# TommyPROM-8755A_Nano.net
KiCad netlist of a schematic drawn in EAGLE
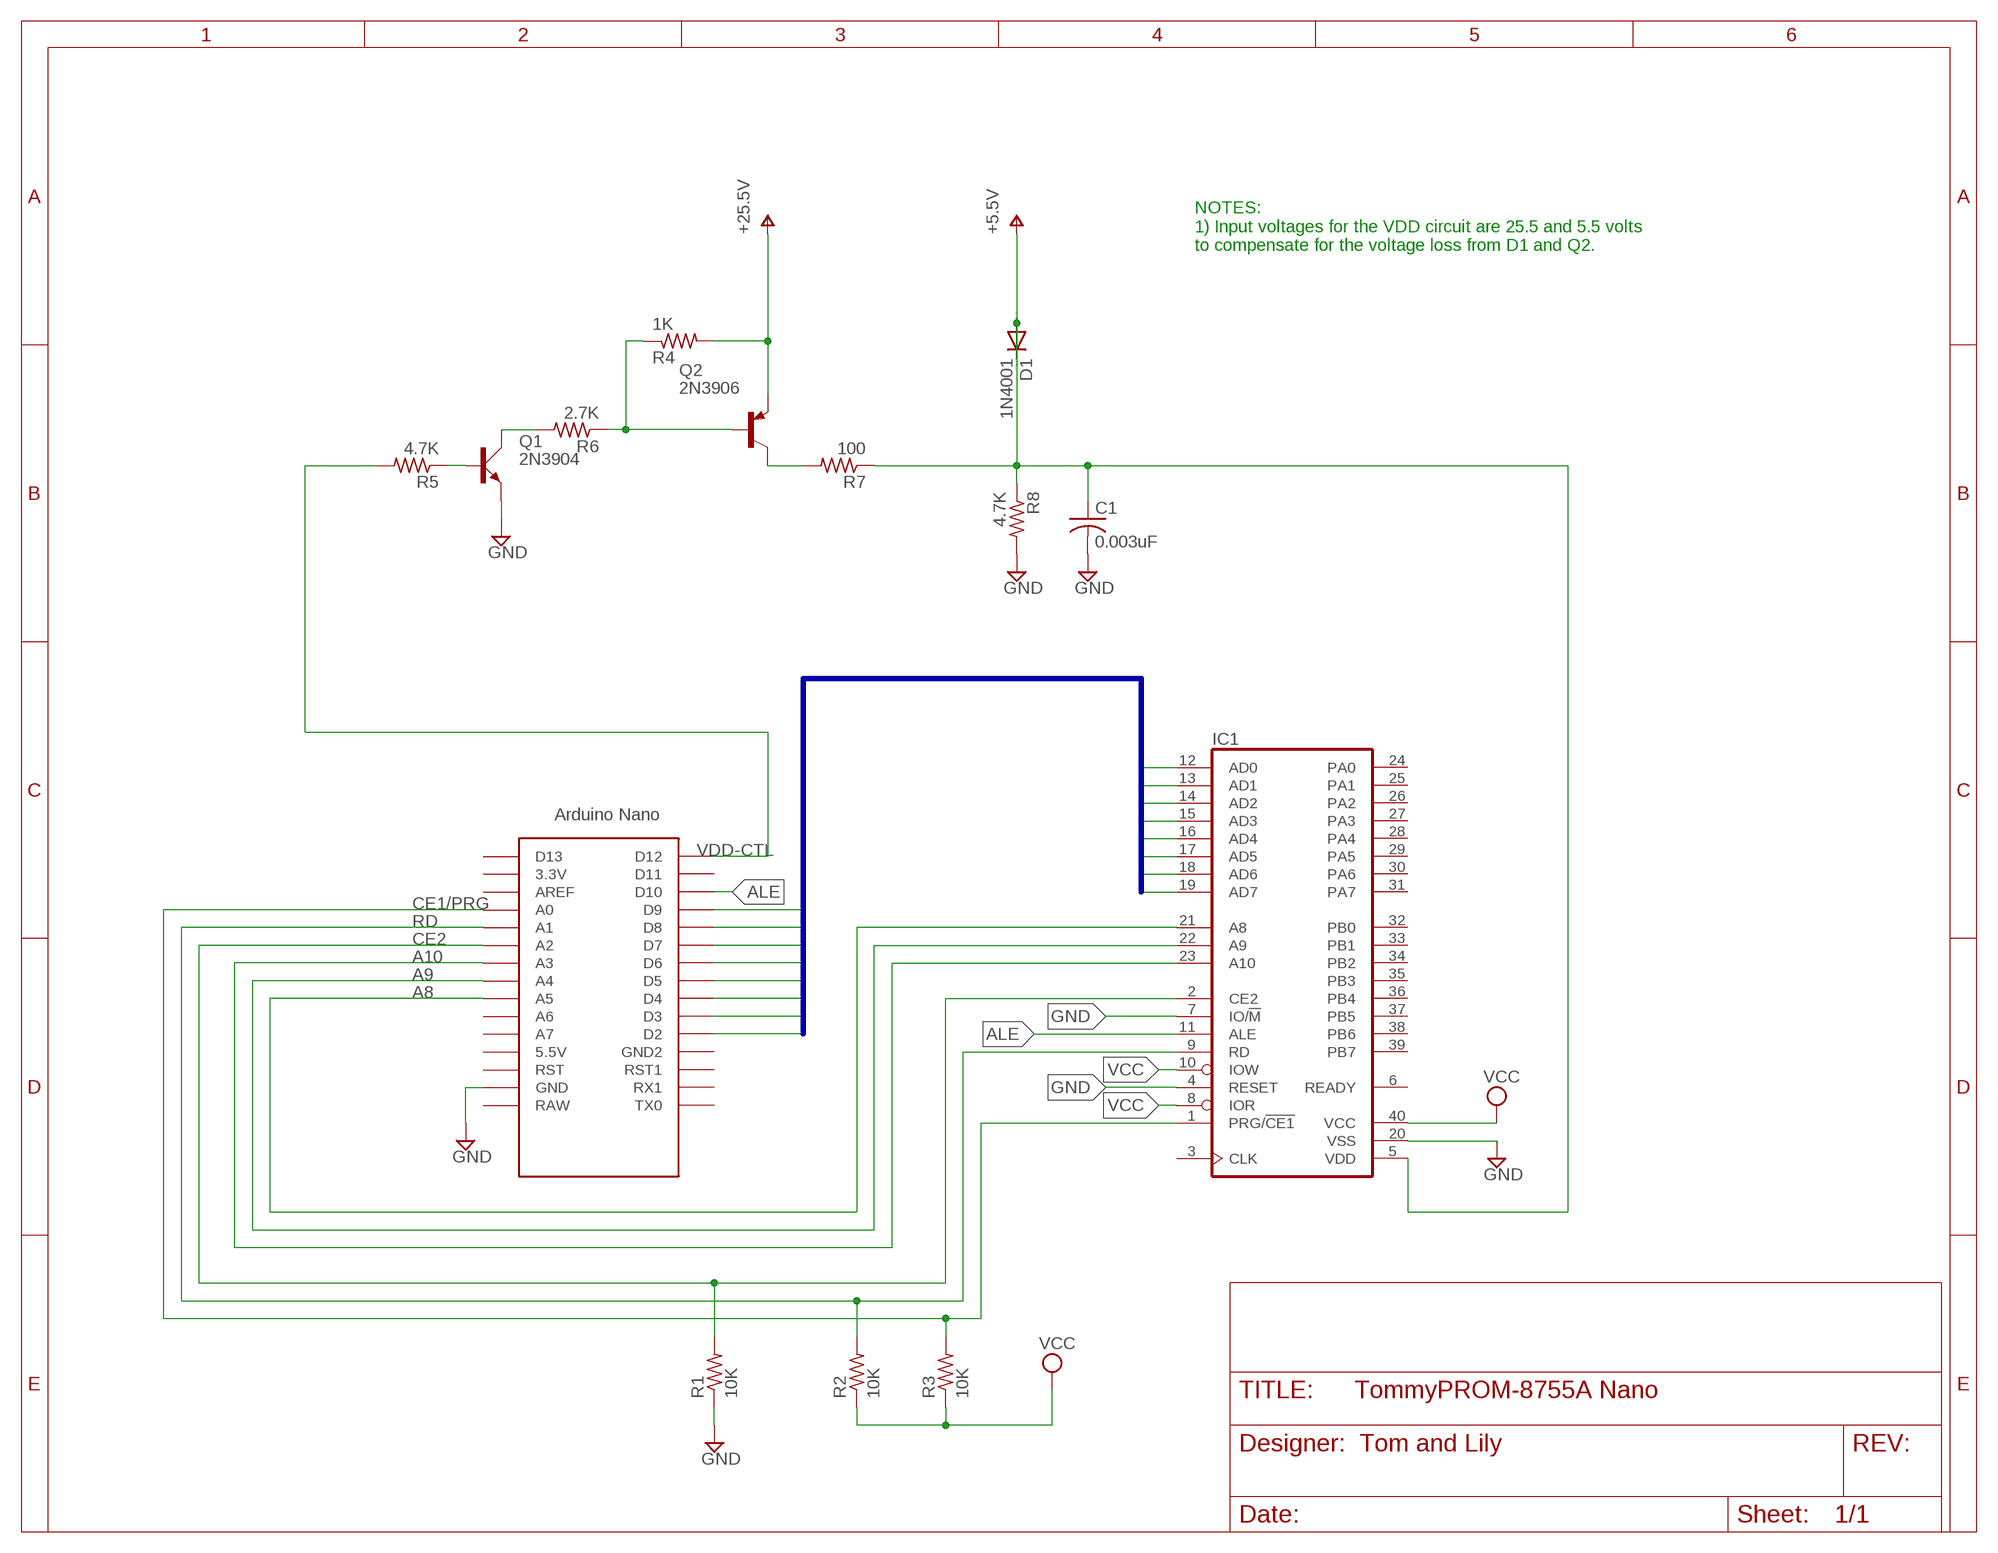
[diagram p0: schematic, sheet 1]

(export (version "E")
  (design (tool "Eeschema 10.0.6"))
  (components
    (comp (ref "C1")
      (value "0.003uF")
      (footprint "eagle-import:C025-024X044")
      (libsource (lib "eagle-import") (part "C-US025-024X044"))
    )
    (comp (ref "D1")
      (value "1N4001")
      (footprint "eagle-import:DO41-10")
      (libsource (lib "eagle-import") (part "1N4004"))
    )
    (comp (ref "IC1")
      (value "8755")
      (footprint "eagle-import:DIL40")
      (libsource (lib "eagle-import") (part "8755"))
    )
    (comp (ref "Q1")
      (value "2N3904")
      (footprint "eagle-import:TO92D")
      (libsource (lib "eagle-import") (part "2N3904"))
    )
    (comp (ref "Q2")
      (value "2N3906")
      (footprint "eagle-import:TO92")
      (libsource (lib "eagle-import") (part "2N3906"))
    )
    (comp (ref "R1")
      (value "10K")
      (footprint "eagle-import:0204_5")
      (libsource (lib "eagle-import") (part "R-US_0204/5"))
    )
    (comp (ref "R2")
      (value "10K")
      (footprint "eagle-import:0204_5")
      (libsource (lib "eagle-import") (part "R-US_0204/5"))
    )
    (comp (ref "R3")
      (value "10K")
      (footprint "eagle-import:0204_5")
      (libsource (lib "eagle-import") (part "R-US_0204/5"))
    )
    (comp (ref "R4")
      (value "1K")
      (footprint "eagle-import:0204_5")
      (libsource (lib "eagle-import") (part "R-US_0204/5"))
    )
    (comp (ref "R5")
      (value "4.7K")
      (footprint "eagle-import:0204_5")
      (libsource (lib "eagle-import") (part "R-US_0204/5"))
    )
    (comp (ref "R6")
      (value "2.7K")
      (footprint "eagle-import:0204_5")
      (libsource (lib "eagle-import") (part "R-US_0204/5"))
    )
    (comp (ref "R7")
      (value "100")
      (footprint "eagle-import:0204_5")
      (libsource (lib "eagle-import") (part "R-US_0204/5"))
    )
    (comp (ref "R8")
      (value "4.7K")
      (footprint "eagle-import:0204_5")
      (libsource (lib "eagle-import") (part "R-US_0204/5"))
    )
    (comp (ref "U$2")
      (value "NANO")
      (footprint "eagle-import:NANO")
      (libsource (lib "eagle-import") (part "NANO"))
    )
  )
  (nets
    (net (code "1") (name "+25.5V") (class "Default")
      (node (ref "C1") (pin "1") (pinfunction "1_1") (pintype "passive"))
      (node (ref "D1") (pin "A") (pinfunction "A_A") (pintype "passive"))
      (node (ref "D1") (pin "C") (pinfunction "C_C") (pintype "passive"))
      (node (ref "IC1") (pin "5") (pinfunction "VDD_5") (pintype "power_in"))
      (node (ref "Q2") (pin "3") (pinfunction "E_3") (pintype "passive"))
      (node (ref "R4") (pin "2") (pinfunction "2_2") (pintype "passive"))
      (node (ref "R7") (pin "1") (pinfunction "1_1") (pintype "passive"))
      (node (ref "R8") (pin "1") (pinfunction "1_1") (pintype "passive"))
    )
    (net (code "2") (name "/A8") (class "Default")
      (node (ref "IC1") (pin "21") (pinfunction "A8_21") (pintype "bidirectional"))
      (node (ref "U$2") (pin "A5") (pinfunction "A5_A5") (pintype "bidirectional"))
    )
    (net (code "3") (name "/A9") (class "Default")
      (node (ref "IC1") (pin "22") (pinfunction "A9_22") (pintype "bidirectional"))
      (node (ref "U$2") (pin "A4") (pinfunction "A4_A4") (pintype "bidirectional"))
    )
    (net (code "4") (name "/A10") (class "Default")
      (node (ref "IC1") (pin "23") (pinfunction "A10_23") (pintype "bidirectional"))
      (node (ref "U$2") (pin "A3") (pinfunction "A3_A3") (pintype "bidirectional"))
    )
    (net (code "5") (name "/CE1{slash}PRG") (class "Default")
      (node (ref "IC1") (pin "1") (pinfunction "PRG/~{CE1}_1") (pintype "input"))
      (node (ref "R3") (pin "2") (pinfunction "2_2") (pintype "passive"))
      (node (ref "U$2") (pin "A0") (pinfunction "A0_A0") (pintype "bidirectional"))
    )
    (net (code "6") (name "/CE2") (class "Default")
      (node (ref "IC1") (pin "2") (pinfunction "CE2_2") (pintype "input"))
      (node (ref "R1") (pin "2") (pinfunction "2_2") (pintype "passive"))
      (node (ref "U$2") (pin "A2") (pinfunction "A2_A2") (pintype "bidirectional"))
    )
    (net (code "7") (name "/D0") (class "Default")
      (node (ref "IC1") (pin "12") (pinfunction "AD0_12") (pintype "bidirectional"))
      (node (ref "U$2") (pin "D2") (pinfunction "D2_D2") (pintype "bidirectional"))
    )
    (net (code "8") (name "/D1") (class "Default")
      (node (ref "IC1") (pin "13") (pinfunction "AD1_13") (pintype "bidirectional"))
      (node (ref "U$2") (pin "D3") (pinfunction "D3_D3") (pintype "bidirectional"))
    )
    (net (code "9") (name "/D2") (class "Default")
      (node (ref "IC1") (pin "14") (pinfunction "AD2_14") (pintype "bidirectional"))
      (node (ref "U$2") (pin "D4") (pinfunction "D4_D4") (pintype "bidirectional"))
    )
    (net (code "10") (name "/D3") (class "Default")
      (node (ref "IC1") (pin "15") (pinfunction "AD3_15") (pintype "bidirectional"))
      (node (ref "U$2") (pin "D5") (pinfunction "D5_D5") (pintype "bidirectional"))
    )
    (net (code "11") (name "/D4") (class "Default")
      (node (ref "IC1") (pin "16") (pinfunction "AD4_16") (pintype "bidirectional"))
      (node (ref "U$2") (pin "D6") (pinfunction "D6_D6") (pintype "bidirectional"))
    )
    (net (code "12") (name "/D5") (class "Default")
      (node (ref "IC1") (pin "17") (pinfunction "AD5_17") (pintype "bidirectional"))
      (node (ref "U$2") (pin "D7") (pinfunction "D7_D7") (pintype "bidirectional"))
    )
    (net (code "13") (name "/D6") (class "Default")
      (node (ref "IC1") (pin "18") (pinfunction "AD6_18") (pintype "bidirectional"))
      (node (ref "U$2") (pin "D8") (pinfunction "D8_D8") (pintype "bidirectional"))
    )
    (net (code "14") (name "/D7") (class "Default")
      (node (ref "IC1") (pin "19") (pinfunction "AD7_19") (pintype "bidirectional"))
      (node (ref "U$2") (pin "D9") (pinfunction "D9_D9") (pintype "bidirectional"))
    )
    (net (code "16") (name "/RD") (class "Default")
      (node (ref "IC1") (pin "9") (pinfunction "RD_9") (pintype "input"))
      (node (ref "R2") (pin "2") (pinfunction "2_2") (pintype "passive"))
      (node (ref "U$2") (pin "A1") (pinfunction "A1_A1") (pintype "bidirectional"))
    )
    (net (code "17") (name "/VDD-CTL") (class "Default")
      (node (ref "R5") (pin "2") (pinfunction "2_2") (pintype "passive"))
      (node (ref "U$2") (pin "D12") (pinfunction "D12_D12") (pintype "bidirectional"))
    )
    (net (code "18") (name "ALE") (class "Default")
      (node (ref "IC1") (pin "11") (pinfunction "ALE_11") (pintype "input"))
      (node (ref "U$2") (pin "D10") (pinfunction "D10_D10") (pintype "bidirectional"))
    )
    (net (code "19") (name "GND") (class "Default")
      (node (ref "C1") (pin "2") (pinfunction "2_2") (pintype "passive"))
      (node (ref "IC1") (pin "20") (pinfunction "VSS_20") (pintype "power_in"))
      (node (ref "IC1") (pin "4") (pinfunction "RESET_4") (pintype "input"))
      (node (ref "IC1") (pin "7") (pinfunction "IO/~{M}_7") (pintype "input"))
      (node (ref "Q1") (pin "E") (pinfunction "E_E") (pintype "passive"))
      (node (ref "R1") (pin "1") (pinfunction "1_1") (pintype "passive"))
      (node (ref "R8") (pin "2") (pinfunction "2_2") (pintype "passive"))
      (node (ref "U$2") (pin "GND") (pinfunction "GND_GND") (pintype "bidirectional"))
    )
    (net (code "20") (name "Net-(Q1-PadB)") (class "Default")
      (node (ref "Q1") (pin "B") (pinfunction "B_B") (pintype "passive"))
      (node (ref "R5") (pin "1") (pinfunction "1_1") (pintype "passive"))
    )
    (net (code "21") (name "Net-(Q1-PadC)") (class "Default")
      (node (ref "Q1") (pin "C") (pinfunction "C_C") (pintype "passive"))
      (node (ref "R6") (pin "2") (pinfunction "2_2") (pintype "passive"))
    )
    (net (code "22") (name "Net-(Q2-B)") (class "Default")
      (node (ref "Q2") (pin "2") (pinfunction "B_2") (pintype "passive"))
      (node (ref "R4") (pin "1") (pinfunction "1_1") (pintype "passive"))
      (node (ref "R6") (pin "1") (pinfunction "1_1") (pintype "passive"))
    )
    (net (code "23") (name "Net-(Q2-C)") (class "Default")
      (node (ref "Q2") (pin "1") (pinfunction "C_1") (pintype "passive"))
      (node (ref "R7") (pin "2") (pinfunction "2_2") (pintype "passive"))
    )
    (net (code "24") (name "VCC") (class "Default")
      (node (ref "IC1") (pin "10") (pinfunction "IOW_10") (pintype "input"))
      (node (ref "IC1") (pin "40") (pinfunction "VCC_40") (pintype "power_in"))
      (node (ref "IC1") (pin "8") (pinfunction "IOR_8") (pintype "input"))
      (node (ref "R2") (pin "1") (pinfunction "1_1") (pintype "passive"))
      (node (ref "R3") (pin "1") (pinfunction "1_1") (pintype "passive"))
    )
    (net (code "25") (name "unconnected-(IC1-CLK-Pad3)") (class "Default")
      (node (ref "IC1") (pin "3") (pinfunction "CLK_3") (pintype "input"))
    )
    (net (code "26") (name "unconnected-(IC1-PA0-Pad24)") (class "Default")
      (node (ref "IC1") (pin "24") (pinfunction "PA0_24") (pintype "bidirectional"))
    )
    (net (code "27") (name "unconnected-(IC1-PA1-Pad25)") (class "Default")
      (node (ref "IC1") (pin "25") (pinfunction "PA1_25") (pintype "bidirectional"))
    )
    (net (code "28") (name "unconnected-(IC1-PA2-Pad26)") (class "Default")
      (node (ref "IC1") (pin "26") (pinfunction "PA2_26") (pintype "bidirectional"))
    )
    (net (code "29") (name "unconnected-(IC1-PA3-Pad27)") (class "Default")
      (node (ref "IC1") (pin "27") (pinfunction "PA3_27") (pintype "bidirectional"))
    )
    (net (code "30") (name "unconnected-(IC1-PA4-Pad28)") (class "Default")
      (node (ref "IC1") (pin "28") (pinfunction "PA4_28") (pintype "bidirectional"))
    )
    (net (code "31") (name "unconnected-(IC1-PA5-Pad29)") (class "Default")
      (node (ref "IC1") (pin "29") (pinfunction "PA5_29") (pintype "bidirectional"))
    )
    (net (code "32") (name "unconnected-(IC1-PA6-Pad30)") (class "Default")
      (node (ref "IC1") (pin "30") (pinfunction "PA6_30") (pintype "bidirectional"))
    )
    (net (code "33") (name "unconnected-(IC1-PA7-Pad31)") (class "Default")
      (node (ref "IC1") (pin "31") (pinfunction "PA7_31") (pintype "bidirectional"))
    )
    (net (code "34") (name "unconnected-(IC1-PB0-Pad32)") (class "Default")
      (node (ref "IC1") (pin "32") (pinfunction "PB0_32") (pintype "bidirectional"))
    )
    (net (code "35") (name "unconnected-(IC1-PB1-Pad33)") (class "Default")
      (node (ref "IC1") (pin "33") (pinfunction "PB1_33") (pintype "bidirectional"))
    )
    (net (code "36") (name "unconnected-(IC1-PB2-Pad34)") (class "Default")
      (node (ref "IC1") (pin "34") (pinfunction "PB2_34") (pintype "bidirectional"))
    )
    (net (code "37") (name "unconnected-(IC1-PB3-Pad35)") (class "Default")
      (node (ref "IC1") (pin "35") (pinfunction "PB3_35") (pintype "bidirectional"))
    )
    (net (code "38") (name "unconnected-(IC1-PB4-Pad36)") (class "Default")
      (node (ref "IC1") (pin "36") (pinfunction "PB4_36") (pintype "bidirectional"))
    )
    (net (code "39") (name "unconnected-(IC1-PB5-Pad37)") (class "Default")
      (node (ref "IC1") (pin "37") (pinfunction "PB5_37") (pintype "bidirectional"))
    )
    (net (code "40") (name "unconnected-(IC1-PB6-Pad38)") (class "Default")
      (node (ref "IC1") (pin "38") (pinfunction "PB6_38") (pintype "bidirectional"))
    )
    (net (code "41") (name "unconnected-(IC1-PB7-Pad39)") (class "Default")
      (node (ref "IC1") (pin "39") (pinfunction "PB7_39") (pintype "bidirectional"))
    )
    (net (code "42") (name "unconnected-(IC1-READY-Pad6)") (class "Default")
      (node (ref "IC1") (pin "6") (pinfunction "READY_6") (pintype "output"))
    )
    (net (code "43") (name "unconnected-(U$2-5.5V-Pad5V)") (class "Default")
      (node (ref "U$2") (pin "5V") (pinfunction "5.5V_5V") (pintype "bidirectional"))
    )
    (net (code "44") (name "unconnected-(U$2-GND2-PadGND1)") (class "Default")
      (node (ref "U$2") (pin "GND1") (pinfunction "GND2_GND1") (pintype "bidirectional"))
    )
    (net (code "45") (name "unconnected-(U$2-Pad3.3V)") (class "Default")
      (node (ref "U$2") (pin "3.3V") (pinfunction "3.3V_3.3V") (pintype "bidirectional"))
    )
    (net (code "46") (name "unconnected-(U$2-PadA6)") (class "Default")
      (node (ref "U$2") (pin "A6") (pinfunction "A6_A6") (pintype "bidirectional"))
    )
    (net (code "47") (name "unconnected-(U$2-PadA7)") (class "Default")
      (node (ref "U$2") (pin "A7") (pinfunction "A7_A7") (pintype "bidirectional"))
    )
    (net (code "48") (name "unconnected-(U$2-PadAREF)") (class "Default")
      (node (ref "U$2") (pin "AREF") (pinfunction "AREF_AREF") (pintype "bidirectional"))
    )
    (net (code "49") (name "unconnected-(U$2-PadD11)") (class "Default")
      (node (ref "U$2") (pin "D11") (pinfunction "D11_D11") (pintype "bidirectional"))
    )
    (net (code "50") (name "unconnected-(U$2-PadD13)") (class "Default")
      (node (ref "U$2") (pin "D13") (pinfunction "D13_D13") (pintype "bidirectional"))
    )
    (net (code "51") (name "unconnected-(U$2-PadICSP1)") (class "Default")
      (node (ref "U$2") (pin "ICSP1") (pinfunction "ICSP1_ICSP1") (pintype "bidirectional"))
    )
    (net (code "52") (name "unconnected-(U$2-PadICSP2)") (class "Default")
      (node (ref "U$2") (pin "ICSP2") (pinfunction "ICSP2_ICSP2") (pintype "bidirectional"))
    )
    (net (code "53") (name "unconnected-(U$2-PadICSP3)") (class "Default")
      (node (ref "U$2") (pin "ICSP3") (pinfunction "ICSP3_ICSP3") (pintype "bidirectional"))
    )
    (net (code "54") (name "unconnected-(U$2-PadICSP4)") (class "Default")
      (node (ref "U$2") (pin "ICSP4") (pinfunction "ICSP4_ICSP4") (pintype "bidirectional"))
    )
    (net (code "55") (name "unconnected-(U$2-PadICSP5)") (class "Default")
      (node (ref "U$2") (pin "ICSP5") (pinfunction "ICSP5_ICSP5") (pintype "bidirectional"))
    )
    (net (code "56") (name "unconnected-(U$2-PadICSP6)") (class "Default")
      (node (ref "U$2") (pin "ICSP6") (pinfunction "ICSP6_ICSP6") (pintype "bidirectional"))
    )
    (net (code "57") (name "unconnected-(U$2-PadRAW)") (class "Default")
      (node (ref "U$2") (pin "RAW") (pinfunction "RAW_RAW") (pintype "bidirectional"))
    )
    (net (code "58") (name "unconnected-(U$2-PadRST)") (class "Default")
      (node (ref "U$2") (pin "RST") (pinfunction "RST_RST") (pintype "bidirectional"))
    )
    (net (code "59") (name "unconnected-(U$2-PadRST1)") (class "Default")
      (node (ref "U$2") (pin "RST1") (pinfunction "RST1_RST1") (pintype "bidirectional"))
    )
    (net (code "60") (name "unconnected-(U$2-PadRX1)") (class "Default")
      (node (ref "U$2") (pin "RX1") (pinfunction "RX1_RX1") (pintype "bidirectional"))
    )
    (net (code "61") (name "unconnected-(U$2-PadTX0)") (class "Default")
      (node (ref "U$2") (pin "TX0") (pinfunction "TX0_TX0") (pintype "bidirectional"))
    )
  )
)
